# FPGA_Power.net
KiCad netlist of a schematic drawn in Altium Designer
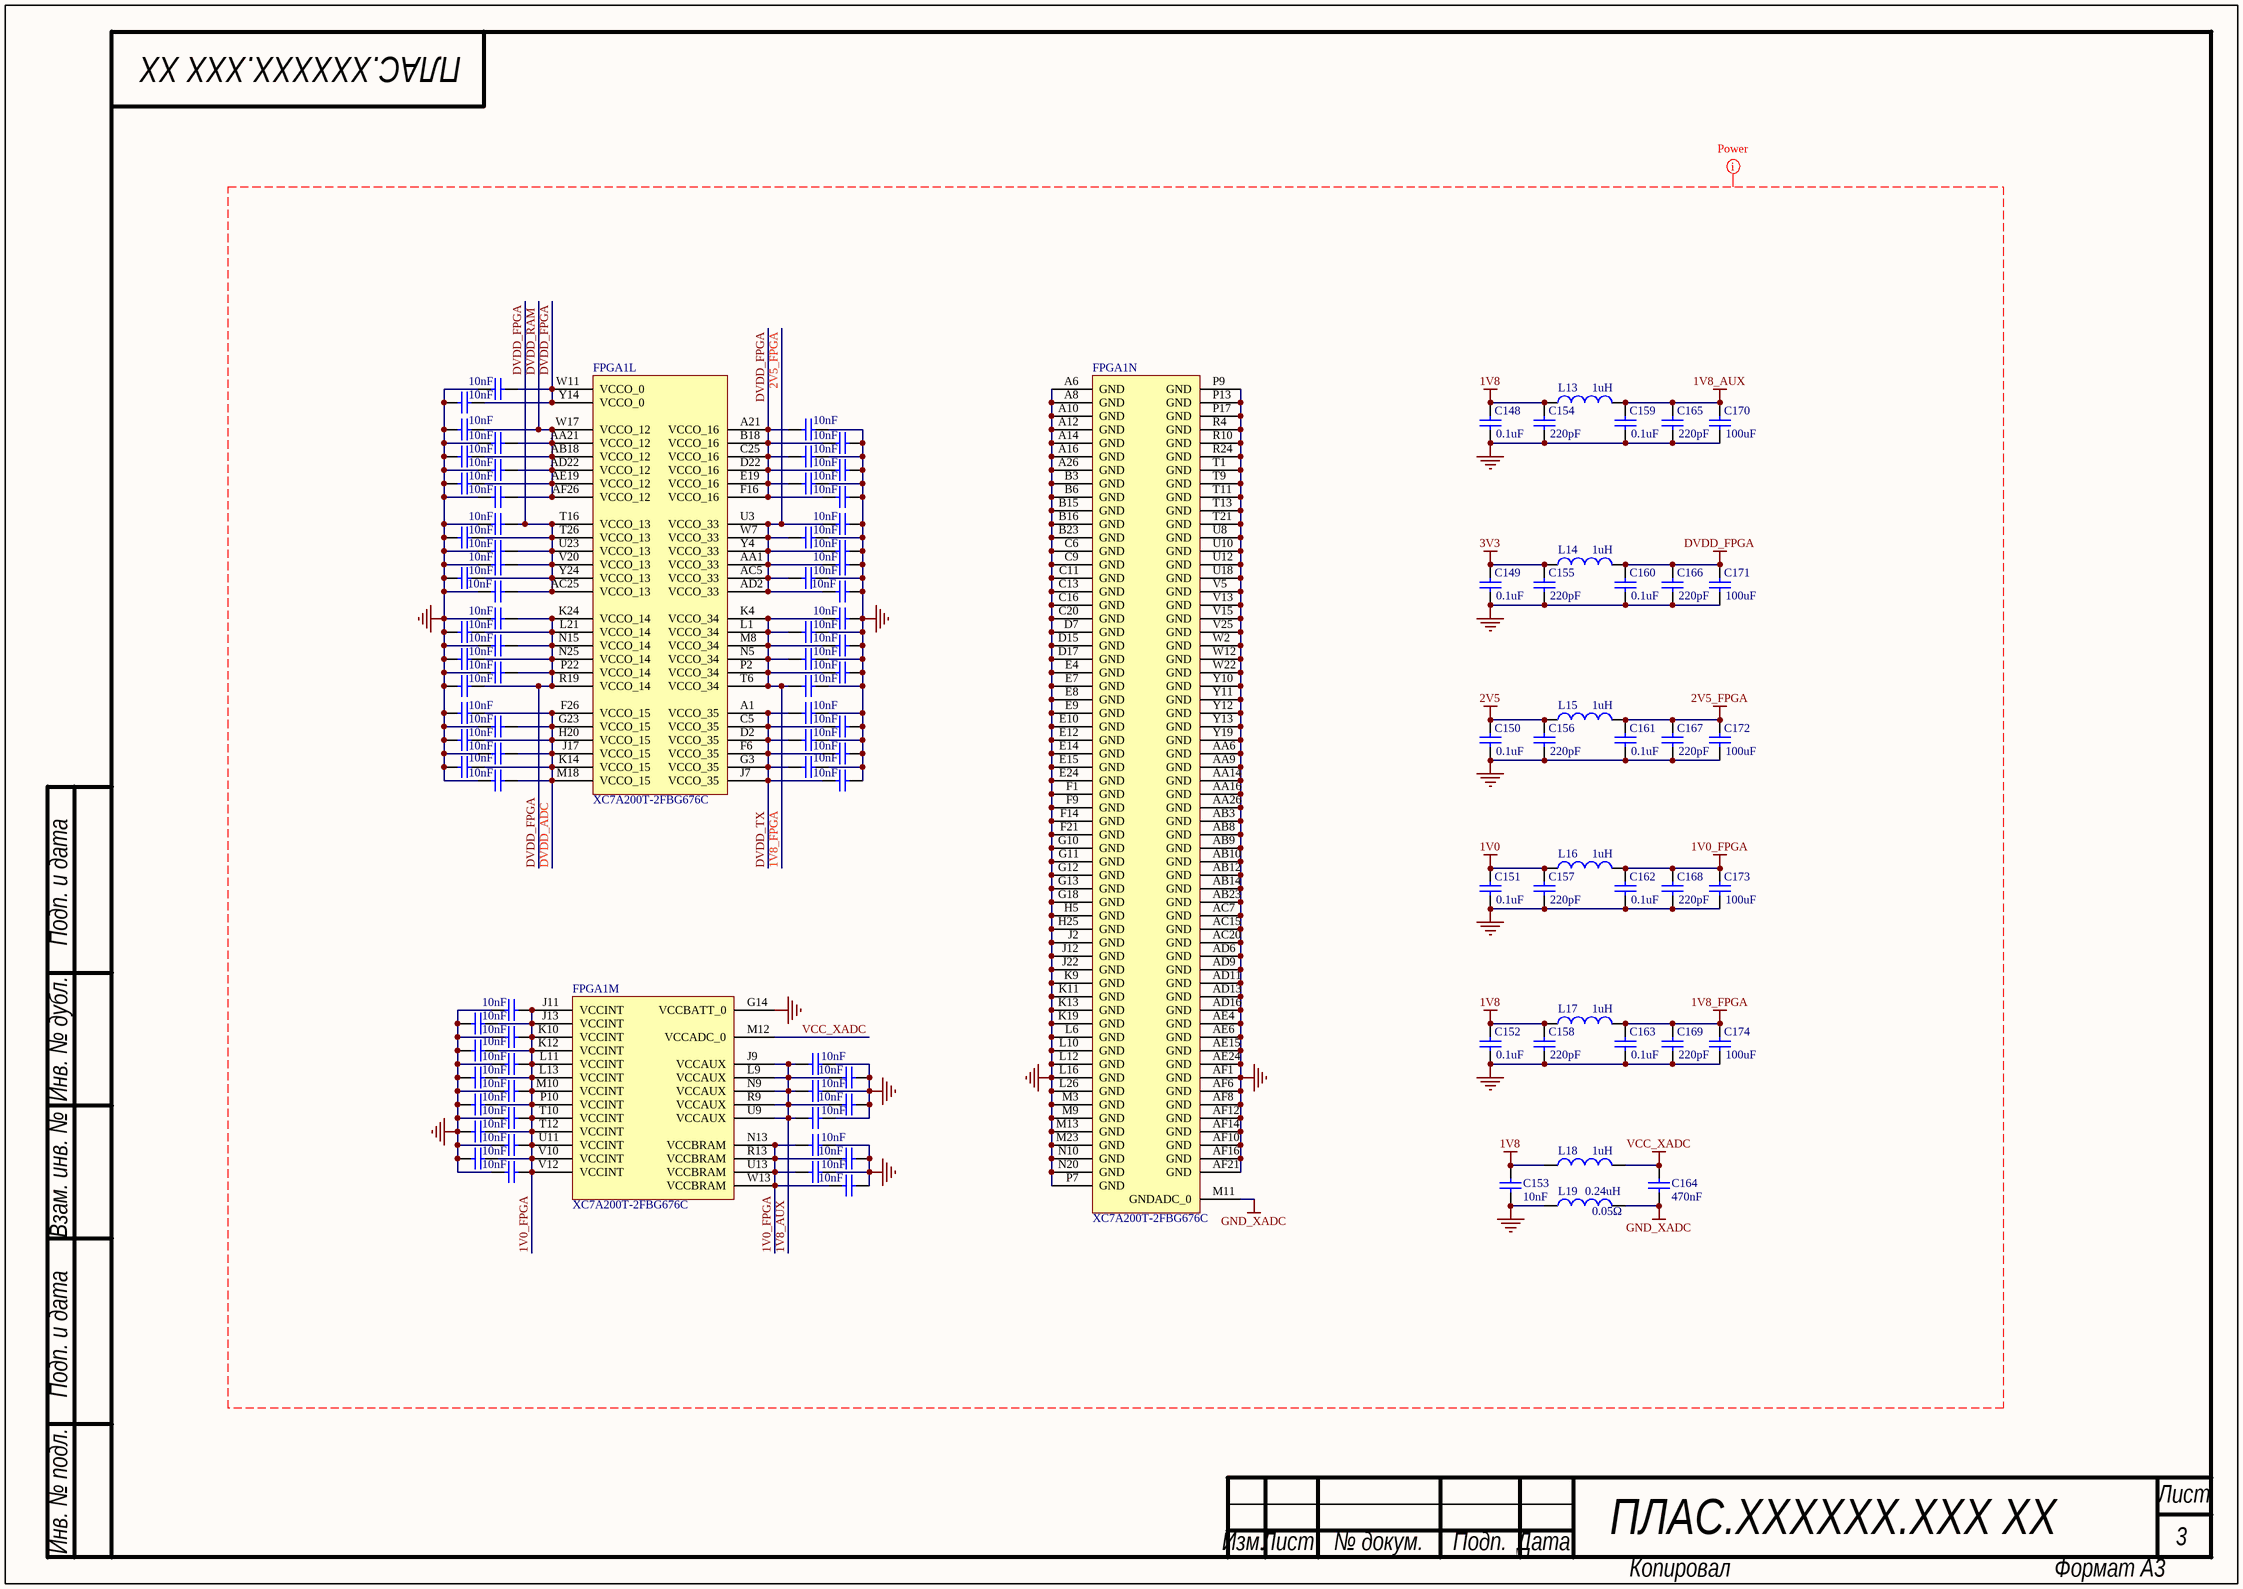
[diagram p0: FPGA_Power.SchDoc]

(export (version "E")
  (design (tool "Eeschema 10.0.6"))
  (components
    (comp (ref "C76")
      (value "10nF")
      (footprint "С0402")
      (description "Cer Cap Small")
      (fields (field (name "MANUFACTURER") "Murata") (field (name "VOLTAGE") "25V"))
      (libsource (lib "") (part "Cer Cap_1"))
    )
    (comp (ref "C77")
      (value "10nF")
      (footprint "С0402")
      (description "Cer Cap Small")
      (fields (field (name "MANUFACTURER") "Murata") (field (name "VOLTAGE") "25V"))
      (libsource (lib "USRP2_Clone") (part "Cer Cap"))
    )
    (comp (ref "C78")
      (value "10nF")
      (footprint "С0402")
      (description "Cer Cap Small")
      (fields (field (name "MANUFACTURER") "Murata") (field (name "VOLTAGE") "25V"))
      (libsource (lib "USRP2_Clone") (part "Cer Cap"))
    )
    (comp (ref "C79")
      (value "10nF")
      (footprint "С0402")
      (description "Cer Cap Small")
      (fields (field (name "MANUFACTURER") "Murata") (field (name "VOLTAGE") "25V"))
      (libsource (lib "USRP2_Clone") (part "Cer Cap"))
    )
    (comp (ref "C80")
      (value "10nF")
      (footprint "С0402")
      (description "Cer Cap Small")
      (fields (field (name "MANUFACTURER") "Murata") (field (name "VOLTAGE") "25V"))
      (libsource (lib "USRP2_Clone") (part "Cer Cap"))
    )
    (comp (ref "C81")
      (value "10nF")
      (footprint "С0402")
      (description "Cer Cap Small")
      (fields (field (name "MANUFACTURER") "Murata") (field (name "VOLTAGE") "25V"))
      (libsource (lib "USRP2_Clone") (part "Cer Cap"))
    )
    (comp (ref "C82")
      (value "10nF")
      (footprint "С0402")
      (description "Cer Cap Small")
      (fields (field (name "MANUFACTURER") "Murata") (field (name "VOLTAGE") "25V"))
      (libsource (lib "USRP2_Clone") (part "Cer Cap"))
    )
    (comp (ref "C83")
      (value "10nF")
      (footprint "С0402")
      (description "Cer Cap Small")
      (fields (field (name "MANUFACTURER") "Murata") (field (name "VOLTAGE") "25V"))
      (libsource (lib "USRP2_Clone") (part "Cer Cap"))
    )
    (comp (ref "C84")
      (value "10nF")
      (footprint "С0402")
      (description "Cer Cap Small")
      (fields (field (name "MANUFACTURER") "Murata") (field (name "VOLTAGE") "25V"))
      (libsource (lib "USRP2_Clone") (part "Cer Cap"))
    )
    (comp (ref "C85")
      (value "10nF")
      (footprint "С0402")
      (description "Cer Cap Small")
      (fields (field (name "MANUFACTURER") "Murata") (field (name "VOLTAGE") "25V"))
      (libsource (lib "") (part "Cer Cap_1"))
    )
    (comp (ref "C86")
      (value "10nF")
      (footprint "С0402")
      (description "Cer Cap Small")
      (fields (field (name "MANUFACTURER") "Murata") (field (name "VOLTAGE") "25V"))
      (libsource (lib "") (part "Cer Cap_1"))
    )
    (comp (ref "C87")
      (value "10nF")
      (footprint "С0402")
      (description "Cer Cap Small")
      (fields (field (name "MANUFACTURER") "Murata") (field (name "VOLTAGE") "25V"))
      (libsource (lib "") (part "Cer Cap_1"))
    )
    (comp (ref "C88")
      (value "10nF")
      (footprint "С0402")
      (description "Cer Cap Small")
      (fields (field (name "MANUFACTURER") "Murata") (field (name "VOLTAGE") "25V"))
      (libsource (lib "USRP2_Clone") (part "Cer Cap"))
    )
    (comp (ref "C89")
      (value "10nF")
      (footprint "С0402")
      (description "Cer Cap Small")
      (fields (field (name "MANUFACTURER") "Murata") (field (name "VOLTAGE") "25V"))
      (libsource (lib "USRP2_Clone") (part "Cer Cap"))
    )
    (comp (ref "C90")
      (value "10nF")
      (footprint "С0402")
      (description "Cer Cap Small")
      (fields (field (name "MANUFACTURER") "Murata") (field (name "VOLTAGE") "25V"))
      (libsource (lib "USRP2_Clone") (part "Cer Cap"))
    )
    (comp (ref "C91")
      (value "10nF")
      (footprint "С0402")
      (description "Cer Cap Small")
      (fields (field (name "MANUFACTURER") "Murata") (field (name "VOLTAGE") "25V"))
      (libsource (lib "USRP2_Clone") (part "Cer Cap"))
    )
    (comp (ref "C92")
      (value "10nF")
      (footprint "С0402")
      (description "Cer Cap Small")
      (fields (field (name "MANUFACTURER") "Murata") (field (name "VOLTAGE") "25V"))
      (libsource (lib "") (part "Cer Cap_1"))
    )
    (comp (ref "C93")
      (value "10nF")
      (footprint "С0402")
      (description "Cer Cap Small")
      (fields (field (name "MANUFACTURER") "Murata") (field (name "VOLTAGE") "25V"))
      (libsource (lib "USRP2_Clone") (part "Cer Cap"))
    )
    (comp (ref "C94")
      (value "10nF")
      (footprint "С0402")
      (description "Cer Cap Small")
      (fields (field (name "MANUFACTURER") "Murata") (field (name "VOLTAGE") "25V"))
      (libsource (lib "") (part "Cer Cap_1"))
    )
    (comp (ref "C95")
      (value "10nF")
      (footprint "С0402")
      (description "Cer Cap Small")
      (fields (field (name "MANUFACTURER") "Murata") (field (name "VOLTAGE") "25V"))
      (libsource (lib "USRP2_Clone") (part "Cer Cap"))
    )
    (comp (ref "C96")
      (value "10nF")
      (footprint "С0402")
      (description "Cer Cap Small")
      (fields (field (name "MANUFACTURER") "Murata") (field (name "VOLTAGE") "25V"))
      (libsource (lib "USRP2_Clone") (part "Cer Cap"))
    )
    (comp (ref "C97")
      (value "10nF")
      (footprint "С0402")
      (description "Cer Cap Small")
      (fields (field (name "MANUFACTURER") "Murata") (field (name "VOLTAGE") "25V"))
      (libsource (lib "USRP2_Clone") (part "Cer Cap"))
    )
    (comp (ref "C98")
      (value "10nF")
      (footprint "С0402")
      (description "Cer Cap Small")
      (fields (field (name "MANUFACTURER") "Murata") (field (name "VOLTAGE") "25V"))
      (libsource (lib "USRP2_Clone") (part "Cer Cap"))
    )
    (comp (ref "C99")
      (value "10nF")
      (footprint "С0402")
      (description "Cer Cap Small")
      (fields (field (name "MANUFACTURER") "Murata") (field (name "VOLTAGE") "25V"))
      (libsource (lib "") (part "Cer Cap_1"))
    )
    (comp (ref "C100")
      (value "10nF")
      (footprint "С0402")
      (description "Cer Cap Small")
      (fields (field (name "MANUFACTURER") "Murata") (field (name "VOLTAGE") "25V"))
      (libsource (lib "USRP2_Clone") (part "Cer Cap"))
    )
    (comp (ref "C101")
      (value "10nF")
      (footprint "С0402")
      (description "Cer Cap Small")
      (fields (field (name "MANUFACTURER") "Murata") (field (name "VOLTAGE") "25V"))
      (libsource (lib "USRP2_Clone") (part "Cer Cap"))
    )
    (comp (ref "C102")
      (value "10nF")
      (footprint "С0402")
      (description "Cer Cap Small")
      (fields (field (name "MANUFACTURER") "Murata") (field (name "VOLTAGE") "25V"))
      (libsource (lib "USRP2_Clone") (part "Cer Cap"))
    )
    (comp (ref "C103")
      (value "10nF")
      (footprint "С0402")
      (description "Cer Cap Small")
      (fields (field (name "MANUFACTURER") "Murata") (field (name "VOLTAGE") "25V"))
      (libsource (lib "USRP2_Clone") (part "Cer Cap"))
    )
    (comp (ref "C104")
      (value "10nF")
      (footprint "С0402")
      (description "Cer Cap Small")
      (fields (field (name "MANUFACTURER") "Murata") (field (name "VOLTAGE") "25V"))
      (libsource (lib "USRP2_Clone") (part "Cer Cap"))
    )
    (comp (ref "C105")
      (value "10nF")
      (footprint "С0402")
      (description "Cer Cap Small")
      (fields (field (name "MANUFACTURER") "Murata") (field (name "VOLTAGE") "25V"))
      (libsource (lib "") (part "Cer Cap_1"))
    )
    (comp (ref "C106")
      (value "10nF")
      (footprint "С0402")
      (description "Cer Cap Small")
      (fields (field (name "MANUFACTURER") "Murata") (field (name "VOLTAGE") "25V"))
      (libsource (lib "") (part "Cer Cap_1"))
    )
    (comp (ref "C107")
      (value "10nF")
      (footprint "С0402")
      (description "Cer Cap Small")
      (fields (field (name "MANUFACTURER") "Murata") (field (name "VOLTAGE") "25V"))
      (libsource (lib "") (part "Cer Cap_1"))
    )
    (comp (ref "C108")
      (value "10nF")
      (footprint "С0402")
      (description "Cer Cap Small")
      (fields (field (name "MANUFACTURER") "Murata") (field (name "VOLTAGE") "25V"))
      (libsource (lib "") (part "Cer Cap_1"))
    )
    (comp (ref "C109")
      (value "10nF")
      (footprint "С0402")
      (description "Cer Cap Small")
      (fields (field (name "MANUFACTURER") "Murata") (field (name "VOLTAGE") "25V"))
      (libsource (lib "") (part "Cer Cap_1"))
    )
    (comp (ref "C110")
      (value "10nF")
      (footprint "С0402")
      (description "Cer Cap Small")
      (fields (field (name "MANUFACTURER") "Murata") (field (name "VOLTAGE") "25V"))
      (libsource (lib "USRP2_Clone") (part "Cer Cap"))
    )
    (comp (ref "C111")
      (value "10nF")
      (footprint "С0402")
      (description "Cer Cap Small")
      (fields (field (name "MANUFACTURER") "Murata") (field (name "VOLTAGE") "25V"))
      (libsource (lib "") (part "Cer Cap_1"))
    )
    (comp (ref "C112")
      (value "10nF")
      (footprint "С0402")
      (description "Cer Cap Small")
      (fields (field (name "MANUFACTURER") "Murata") (field (name "VOLTAGE") "25V"))
      (libsource (lib "") (part "Cer Cap_1"))
    )
    (comp (ref "C113")
      (value "10nF")
      (footprint "С0402")
      (description "Cer Cap Small")
      (fields (field (name "MANUFACTURER") "Murata") (field (name "VOLTAGE") "25V"))
      (libsource (lib "USRP2_Clone") (part "Cer Cap"))
    )
    (comp (ref "C114")
      (value "10nF")
      (footprint "С0402")
      (description "Cer Cap Small")
      (fields (field (name "MANUFACTURER") "Murata") (field (name "VOLTAGE") "25V"))
      (libsource (lib "USRP2_Clone") (part "Cer Cap"))
    )
    (comp (ref "C115")
      (value "10nF")
      (footprint "С0402")
      (description "Cer Cap Small")
      (fields (field (name "MANUFACTURER") "Murata") (field (name "VOLTAGE") "25V"))
      (libsource (lib "USRP2_Clone") (part "Cer Cap"))
    )
    (comp (ref "C116")
      (value "10nF")
      (footprint "С0402")
      (description "Cer Cap Small")
      (fields (field (name "MANUFACTURER") "Murata") (field (name "VOLTAGE") "25V"))
      (libsource (lib "USRP2_Clone") (part "Cer Cap"))
    )
    (comp (ref "C117")
      (value "10nF")
      (footprint "С0402")
      (description "Cer Cap Small")
      (fields (field (name "MANUFACTURER") "Murata") (field (name "VOLTAGE") "25V"))
      (libsource (lib "USRP2_Clone") (part "Cer Cap"))
    )
    (comp (ref "C118")
      (value "10nF")
      (footprint "С0402")
      (description "Cer Cap Small")
      (fields (field (name "MANUFACTURER") "Murata") (field (name "VOLTAGE") "25V"))
      (libsource (lib "USRP2_Clone") (part "Cer Cap"))
    )
    (comp (ref "C119")
      (value "10nF")
      (footprint "С0402")
      (description "Cer Cap Small")
      (fields (field (name "MANUFACTURER") "Murata") (field (name "VOLTAGE") "25V"))
      (libsource (lib "USRP2_Clone") (part "Cer Cap"))
    )
    (comp (ref "C120")
      (value "10nF")
      (footprint "С0402")
      (description "Cer Cap Small")
      (fields (field (name "MANUFACTURER") "Murata") (field (name "VOLTAGE") "25V"))
      (libsource (lib "USRP2_Clone") (part "Cer Cap"))
    )
    (comp (ref "C121")
      (value "10nF")
      (footprint "С0402")
      (description "Cer Cap Small")
      (fields (field (name "MANUFACTURER") "Murata") (field (name "VOLTAGE") "25V"))
      (libsource (lib "USRP2_Clone") (part "Cer Cap"))
    )
    (comp (ref "C122")
      (value "10nF")
      (footprint "С0402")
      (description "Cer Cap Small")
      (fields (field (name "MANUFACTURER") "Murata") (field (name "VOLTAGE") "25V"))
      (libsource (lib "USRP2_Clone") (part "Cer Cap"))
    )
    (comp (ref "C123")
      (value "10nF")
      (footprint "С0402")
      (description "Cer Cap Small")
      (fields (field (name "MANUFACTURER") "Murata") (field (name "VOLTAGE") "25V"))
      (libsource (lib "USRP2_Clone") (part "Cer Cap"))
    )
    (comp (ref "C124")
      (value "10nF")
      (footprint "С0402")
      (description "Cer Cap Small")
      (fields (field (name "MANUFACTURER") "Murata") (field (name "VOLTAGE") "25V"))
      (libsource (lib "USRP2_Clone") (part "Cer Cap"))
    )
    (comp (ref "C125")
      (value "10nF")
      (footprint "С0402")
      (description "Cer Cap Small")
      (fields (field (name "MANUFACTURER") "Murata") (field (name "VOLTAGE") "25V"))
      (libsource (lib "USRP2_Clone") (part "Cer Cap"))
    )
    (comp (ref "C126")
      (value "10nF")
      (footprint "С0402")
      (description "Cer Cap Small")
      (fields (field (name "MANUFACTURER") "Murata") (field (name "VOLTAGE") "25V"))
      (libsource (lib "") (part "Cer Cap_1"))
    )
    (comp (ref "C127")
      (value "10nF")
      (footprint "С0402")
      (description "Cer Cap Small")
      (fields (field (name "MANUFACTURER") "Murata") (field (name "VOLTAGE") "25V"))
      (libsource (lib "") (part "Cer Cap_1"))
    )
    (comp (ref "C128")
      (value "10nF")
      (footprint "С0402")
      (description "Cer Cap Small")
      (fields (field (name "MANUFACTURER") "Murata") (field (name "VOLTAGE") "25V"))
      (libsource (lib "USRP2_Clone") (part "Cer Cap"))
    )
    (comp (ref "C129")
      (value "10nF")
      (footprint "С0402")
      (description "Cer Cap Small")
      (fields (field (name "MANUFACTURER") "Murata") (field (name "VOLTAGE") "25V"))
      (libsource (lib "") (part "Cer Cap_1"))
    )
    (comp (ref "C130")
      (value "10nF")
      (footprint "С0402")
      (description "Cer Cap Small")
      (fields (field (name "MANUFACTURER") "Murata") (field (name "VOLTAGE") "25V"))
      (libsource (lib "USRP2_Clone") (part "Cer Cap"))
    )
    (comp (ref "C131")
      (value "10nF")
      (footprint "С0402")
      (description "Cer Cap Small")
      (fields (field (name "MANUFACTURER") "Murata") (field (name "VOLTAGE") "25V"))
      (libsource (lib "USRP2_Clone") (part "Cer Cap"))
    )
    (comp (ref "C132")
      (value "10nF")
      (footprint "С0402")
      (description "Cer Cap Small")
      (fields (field (name "MANUFACTURER") "Murata") (field (name "VOLTAGE") "25V"))
      (libsource (lib "USRP2_Clone") (part "Cer Cap"))
    )
    (comp (ref "C133")
      (value "10nF")
      (footprint "С0402")
      (description "Cer Cap Small")
      (fields (field (name "MANUFACTURER") "Murata") (field (name "VOLTAGE") "25V"))
      (libsource (lib "USRP2_Clone") (part "Cer Cap"))
    )
    (comp (ref "C134")
      (value "10nF")
      (footprint "С0402")
      (description "Cer Cap Small")
      (fields (field (name "MANUFACTURER") "Murata") (field (name "VOLTAGE") "25V"))
      (libsource (lib "USRP2_Clone") (part "Cer Cap"))
    )
    (comp (ref "C135")
      (value "10nF")
      (footprint "С0402")
      (description "Cer Cap Small")
      (fields (field (name "MANUFACTURER") "Murata") (field (name "VOLTAGE") "25V"))
      (libsource (lib "USRP2_Clone") (part "Cer Cap"))
    )
    (comp (ref "C136")
      (value "10nF")
      (footprint "С0402")
      (description "Cer Cap Small")
      (fields (field (name "MANUFACTURER") "Murata") (field (name "VOLTAGE") "25V"))
      (libsource (lib "") (part "Cer Cap_1"))
    )
    (comp (ref "C137")
      (value "10nF")
      (footprint "С0402")
      (description "Cer Cap Small")
      (fields (field (name "MANUFACTURER") "Murata") (field (name "VOLTAGE") "25V"))
      (libsource (lib "USRP2_Clone") (part "Cer Cap"))
    )
    (comp (ref "C138")
      (value "10nF")
      (footprint "С0402")
      (description "Cer Cap Small")
      (fields (field (name "MANUFACTURER") "Murata") (field (name "VOLTAGE") "25V"))
      (libsource (lib "USRP2_Clone") (part "Cer Cap"))
    )
    (comp (ref "C139")
      (value "10nF")
      (footprint "С0402")
      (description "Cer Cap Small")
      (fields (field (name "MANUFACTURER") "Murata") (field (name "VOLTAGE") "25V"))
      (libsource (lib "USRP2_Clone") (part "Cer Cap"))
    )
    (comp (ref "C140")
      (value "10nF")
      (footprint "С0402")
      (description "Cer Cap Small")
      (fields (field (name "MANUFACTURER") "Murata") (field (name "VOLTAGE") "25V"))
      (libsource (lib "USRP2_Clone") (part "Cer Cap"))
    )
    (comp (ref "C141")
      (value "10nF")
      (footprint "С0402")
      (description "Cer Cap Small")
      (fields (field (name "MANUFACTURER") "Murata") (field (name "VOLTAGE") "25V"))
      (libsource (lib "USRP2_Clone") (part "Cer Cap"))
    )
    (comp (ref "C142")
      (value "10nF")
      (footprint "С0402")
      (description "Cer Cap Small")
      (fields (field (name "MANUFACTURER") "Murata") (field (name "VOLTAGE") "25V"))
      (libsource (lib "USRP2_Clone") (part "Cer Cap"))
    )
    (comp (ref "C143")
      (value "10nF")
      (footprint "С0402")
      (description "Cer Cap Small")
      (fields (field (name "MANUFACTURER") "Murata") (field (name "VOLTAGE") "25V"))
      (libsource (lib "USRP2_Clone") (part "Cer Cap"))
    )
    (comp (ref "C144")
      (value "10nF")
      (footprint "С0402")
      (description "Cer Cap Small")
      (fields (field (name "MANUFACTURER") "Murata") (field (name "VOLTAGE") "25V"))
      (libsource (lib "") (part "Cer Cap_1"))
    )
    (comp (ref "C145")
      (value "10nF")
      (footprint "С0402")
      (description "Cer Cap Small")
      (fields (field (name "MANUFACTURER") "Murata") (field (name "VOLTAGE") "25V"))
      (libsource (lib "USRP2_Clone") (part "Cer Cap"))
    )
    (comp (ref "C146")
      (value "10nF")
      (footprint "С0402")
      (description "Cer Cap Small")
      (fields (field (name "MANUFACTURER") "Murata") (field (name "VOLTAGE") "25V"))
      (libsource (lib "USRP2_Clone") (part "Cer Cap"))
    )
    (comp (ref "C147")
      (value "10nF")
      (footprint "С0402")
      (description "Cer Cap Small")
      (fields (field (name "MANUFACTURER") "Murata") (field (name "VOLTAGE") "25V"))
      (libsource (lib "USRP2_Clone") (part "Cer Cap"))
    )
    (comp (ref "C148")
      (value "0.1uF")
      (footprint "C0603")
      (description "Cer Cap Small")
      (fields (field (name "MANUFACTURER") "Murata") (field (name "VOLTAGE") "16V"))
      (libsource (lib "") (part "Cer Cap_1"))
    )
    (comp (ref "C149")
      (value "0.1uF")
      (footprint "C0603")
      (description "Cer Cap Small")
      (fields (field (name "MANUFACTURER") "Murata") (field (name "VOLTAGE") "16V"))
      (libsource (lib "") (part "Cer Cap_1"))
    )
    (comp (ref "C150")
      (value "0.1uF")
      (footprint "C0603")
      (description "Cer Cap Small")
      (fields (field (name "MANUFACTURER") "Murata") (field (name "VOLTAGE") "16V"))
      (libsource (lib "") (part "Cer Cap_1"))
    )
    (comp (ref "C151")
      (value "0.1uF")
      (footprint "C0603")
      (description "Cer Cap Small")
      (fields (field (name "MANUFACTURER") "Murata") (field (name "VOLTAGE") "16V"))
      (libsource (lib "") (part "Cer Cap_1"))
    )
    (comp (ref "C152")
      (value "0.1uF")
      (footprint "C0603")
      (description "Cer Cap Small")
      (fields (field (name "MANUFACTURER") "Murata") (field (name "VOLTAGE") "16V"))
      (libsource (lib "USRP2_Clone") (part "Cer Cap"))
    )
    (comp (ref "C153")
      (value "10nF")
      (footprint "С0402")
      (description "Cer Cap Small")
      (fields (field (name "MANUFACTURER") "Murata") (field (name "VOLTAGE") "25V"))
      (libsource (lib "USRP2_Clone") (part "Cer Cap"))
    )
    (comp (ref "C154")
      (value "220pF")
      (footprint "C0603")
      (description "Cer Cap Small")
      (fields (field (name "MANUFACTURER") "Murata") (field (name "VOLTAGE") "16V"))
      (libsource (lib "") (part "Cer Cap_1"))
    )
    (comp (ref "C155")
      (value "220pF")
      (footprint "C0603")
      (description "Cer Cap Small")
      (fields (field (name "MANUFACTURER") "Murata") (field (name "VOLTAGE") "16V"))
      (libsource (lib "") (part "Cer Cap_1"))
    )
    (comp (ref "C156")
      (value "220pF")
      (footprint "C0603")
      (description "Cer Cap Small")
      (fields (field (name "MANUFACTURER") "Murata") (field (name "VOLTAGE") "16V"))
      (libsource (lib "") (part "Cer Cap_1"))
    )
    (comp (ref "C157")
      (value "220pF")
      (footprint "C0603")
      (description "Cer Cap Small")
      (fields (field (name "MANUFACTURER") "Murata") (field (name "VOLTAGE") "16V"))
      (libsource (lib "") (part "Cer Cap_1"))
    )
    (comp (ref "C158")
      (value "220pF")
      (footprint "C0603")
      (description "Cer Cap Small")
      (fields (field (name "MANUFACTURER") "Murata") (field (name "VOLTAGE") "16V"))
      (libsource (lib "") (part "Cer Cap_1"))
    )
    (comp (ref "C159")
      (value "0.1uF")
      (footprint "C0603")
      (description "Cer Cap Small")
      (fields (field (name "MANUFACTURER") "Murata") (field (name "VOLTAGE") "16V"))
      (libsource (lib "") (part "Cer Cap_1"))
    )
    (comp (ref "C160")
      (value "0.1uF")
      (footprint "C0603")
      (description "Cer Cap Small")
      (fields (field (name "MANUFACTURER") "Murata") (field (name "VOLTAGE") "16V"))
      (libsource (lib "") (part "Cer Cap_1"))
    )
    (comp (ref "C161")
      (value "0.1uF")
      (footprint "C0603")
      (description "Cer Cap Small")
      (fields (field (name "MANUFACTURER") "Murata") (field (name "VOLTAGE") "16V"))
      (libsource (lib "") (part "Cer Cap_1"))
    )
    (comp (ref "C162")
      (value "0.1uF")
      (footprint "C0603")
      (description "Cer Cap Small")
      (fields (field (name "MANUFACTURER") "Murata") (field (name "VOLTAGE") "16V"))
      (libsource (lib "") (part "Cer Cap_1"))
    )
    (comp (ref "C163")
      (value "0.1uF")
      (footprint "C0603")
      (description "Cer Cap Small")
      (fields (field (name "MANUFACTURER") "Murata") (field (name "VOLTAGE") "16V"))
      (libsource (lib "") (part "Cer Cap_1"))
    )
    (comp (ref "C164")
      (value "470nF")
      (footprint "C0603")
      (description "Cer Cap Small")
      (fields (field (name "MANUFACTURER") "Murata") (field (name "VOLTAGE") "16V"))
      (libsource (lib "USRP2_Clone") (part "Cer Cap"))
    )
    (comp (ref "C165")
      (value "220pF")
      (footprint "C0603")
      (description "Cer Cap Small")
      (fields (field (name "MANUFACTURER") "Murata") (field (name "VOLTAGE") "16V"))
      (libsource (lib "") (part "Cer Cap_1"))
    )
    (comp (ref "C166")
      (value "220pF")
      (footprint "C0603")
      (description "Cer Cap Small")
      (fields (field (name "MANUFACTURER") "Murata") (field (name "VOLTAGE") "16V"))
      (libsource (lib "") (part "Cer Cap_1"))
    )
    (comp (ref "C167")
      (value "220pF")
      (footprint "C0603")
      (description "Cer Cap Small")
      (fields (field (name "MANUFACTURER") "Murata") (field (name "VOLTAGE") "16V"))
      (libsource (lib "") (part "Cer Cap_1"))
    )
    (comp (ref "C168")
      (value "220pF")
      (footprint "C0603")
      (description "Cer Cap Small")
      (fields (field (name "MANUFACTURER") "Murata") (field (name "VOLTAGE") "16V"))
      (libsource (lib "") (part "Cer Cap_1"))
    )
    (comp (ref "C169")
      (value "220pF")
      (footprint "C0603")
      (description "Cer Cap Small")
      (fields (field (name "MANUFACTURER") "Murata") (field (name "VOLTAGE") "16V"))
      (libsource (lib "") (part "Cer Cap_1"))
    )
    (comp (ref "C170")
      (value "100uF")
      (footprint "C1210")
      (description "Cer Cap Large")
      (fields (field (name "MANUFACTURER") "Murata") (field (name "TOLERANCE") "20%"))
      (libsource (lib "USRP2_Clone") (part "Cap uF"))
    )
    (comp (ref "C171")
      (value "100uF")
      (footprint "C1210")
      (description "Cer Cap Large")
      (fields (field (name "MANUFACTURER") "Murata") (field (name "TOLERANCE") "20%"))
      (libsource (lib "") (part "Cap uF_1"))
    )
    (comp (ref "C172")
      (value "100uF")
      (footprint "C1210")
      (description "Cer Cap Large")
      (fields (field (name "MANUFACTURER") "Murata") (field (name "TOLERANCE") "20%"))
      (libsource (lib "USRP2_Clone") (part "Cap uF"))
    )
    (comp (ref "C173")
      (value "100uF")
      (footprint "C1210")
      (description "Cer Cap Large")
      (fields (field (name "MANUFACTURER") "Murata") (field (name "TOLERANCE") "20%"))
      (libsource (lib "USRP2_Clone") (part "Cap uF"))
    )
    (comp (ref "C174")
      (value "100uF")
      (footprint "C1210")
      (description "Cer Cap Large")
      (fields (field (name "MANUFACTURER") "Murata") (field (name "TOLERANCE") "20%"))
      (libsource (lib "") (part "Cap uF_1"))
    )
    (comp (ref "FPGA1")
      (value "XC7A200T-2FBG676C")
      (footprint "FGG676")
      (description "Artix-7 FPGA, 400 User I/Os, 8 GTP, 676-Ball BGA, Speed Grade 2, Commercial Grade, Pb-Free")
      (fields (field (name "GENERIC PART NUMBER") "XC7A200T") (field (name "MANUFACTURER") "Xilinx"))
      (libsource (lib "USRP2_Clone") (part "XC7A200T-2FBG676C"))
    )
    (comp (ref "L13")
      (value "1uH")
      (footprint "L1210_Murata LQH")
      (description "Inductor_Power_Lines")
      (fields (field (name "TOLERANCE") "5%") (field (name "MANUFACTURER") "Murata"))
      (libsource (lib "USRP2_Clone") (part "Inductor_LF"))
    )
    (comp (ref "L14")
      (value "1uH")
      (footprint "L1210_Murata LQH")
      (description "Inductor_Power_Lines")
      (fields (field (name "TOLERANCE") "5%") (field (name "MANUFACTURER") "Murata"))
      (libsource (lib "") (part "Inductor_LF_1"))
    )
    (comp (ref "L15")
      (value "1uH")
      (footprint "L1210_Murata LQH")
      (description "Inductor_Power_Lines")
      (fields (field (name "TOLERANCE") "5%") (field (name "MANUFACTURER") "Murata"))
      (libsource (lib "USRP2_Clone") (part "Inductor_LF"))
    )
    (comp (ref "L16")
      (value "1uH")
      (footprint "L1210_Murata LQH")
      (description "Inductor_Power_Lines")
      (fields (field (name "TOLERANCE") "5%") (field (name "MANUFACTURER") "Murata"))
      (libsource (lib "USRP2_Clone") (part "Inductor_LF"))
    )
    (comp (ref "L17")
      (value "1uH")
      (footprint "L1210_Murata LQH")
      (description "Inductor_Power_Lines")
      (fields (field (name "TOLERANCE") "5%") (field (name "MANUFACTURER") "Murata"))
      (libsource (lib "USRP2_Clone") (part "Inductor_LF"))
    )
    (comp (ref "L18")
      (value "1uH")
      (footprint "L1206_Murata")
      (description "Inductor_Power_Lines")
      (fields (field (name "TOLERANCE") "5%") (field (name "MANUFACTURER") "Murata"))
      (libsource (lib "USRP2_Clone") (part "Inductor_LF"))
    )
    (comp (ref "L19")
      (value "0.24uH")
      (footprint "L0805_Murata_LQG")
      (description "Inductor_Power_Lines")
      (fields
        (field (name "TOLERANCE") "±20%")
        (field (name "MANUFACTURER") "Murata")
        (field (name "DCR") "0.05Ω")
      )
      (libsource (lib "") (part "Inductor_LF_1"))
    )
  )
  (nets
    (net (code "1") (name "/DVDD_ADC") (class "Default")
      (node (ref "C105") (pin "2") (pinfunction "2_2") (pintype "passive"))
      (node (ref "C106") (pin "2") (pinfunction "2_2") (pintype "passive"))
      (node (ref "C107") (pin "2") (pinfunction "2_2") (pintype "passive"))
      (node (ref "C85") (pin "2") (pinfunction "2_2") (pintype "passive"))
      (node (ref "C86") (pin "2") (pinfunction "2_2") (pintype "passive"))
      (node (ref "C87") (pin "2") (pinfunction "2_2") (pintype "passive"))
      (node (ref "FPGA1") (pin "F26") (pinfunction "VCCO_15_F26") (pintype "power_in"))
      (node (ref "FPGA1") (pin "G23") (pinfunction "VCCO_15_G23") (pintype "power_in"))
      (node (ref "FPGA1") (pin "H20") (pinfunction "VCCO_15_H20") (pintype "power_in"))
      (node (ref "FPGA1") (pin "J17") (pinfunction "VCCO_15_J17") (pintype "power_in"))
      (node (ref "FPGA1") (pin "K14") (pinfunction "VCCO_15_K14") (pintype "power_in"))
      (node (ref "FPGA1") (pin "M18") (pinfunction "VCCO_15_M18") (pintype "power_in"))
    )
    (net (code "2") (name "/DVDD_RAM") (class "Default")
      (node (ref "C77") (pin "1") (pinfunction "1_1") (pintype "passive"))
      (node (ref "C78") (pin "1") (pinfunction "1_1") (pintype "passive"))
      (node (ref "C79") (pin "1") (pinfunction "1_1") (pintype "passive"))
      (node (ref "C95") (pin "1") (pinfunction "1_1") (pintype "passive"))
      (node (ref "C96") (pin "1") (pinfunction "1_1") (pintype "passive"))
      (node (ref "C97") (pin "1") (pinfunction "1_1") (pintype "passive"))
      (node (ref "FPGA1") (pin "AA21") (pinfunction "VCCO_12_AA21") (pintype "power_in"))
      (node (ref "FPGA1") (pin "AB18") (pinfunction "VCCO_12_AB18") (pintype "power_in"))
      (node (ref "FPGA1") (pin "AD22") (pinfunction "VCCO_12_AD22") (pintype "power_in"))
      (node (ref "FPGA1") (pin "AE19") (pinfunction "VCCO_12_AE19") (pintype "power_in"))
      (node (ref "FPGA1") (pin "AF26") (pinfunction "VCCO_12_AF26") (pintype "power_in"))
      (node (ref "FPGA1") (pin "W17") (pinfunction "VCCO_12_W17") (pintype "power_in"))
    )
    (net (code "3") (name "/DVDD_TX") (class "Default")
      (node (ref "C123") (pin "2") (pinfunction "2_2") (pintype "passive"))
      (node (ref "C124") (pin "2") (pinfunction "2_2") (pintype "passive"))
      (node (ref "C125") (pin "2") (pinfunction "2_2") (pintype "passive"))
      (node (ref "C141") (pin "2") (pinfunction "2_2") (pintype "passive"))
      (node (ref "C142") (pin "2") (pinfunction "2_2") (pintype "passive"))
      (node (ref "C143") (pin "2") (pinfunction "2_2") (pintype "passive"))
      (node (ref "FPGA1") (pin "A1") (pinfunction "VCCO_35_A1") (pintype "power_in"))
      (node (ref "FPGA1") (pin "C5") (pinfunction "VCCO_35_C5") (pintype "power_in"))
      (node (ref "FPGA1") (pin "D2") (pinfunction "VCCO_35_D2") (pintype "power_in"))
      (node (ref "FPGA1") (pin "F6") (pinfunction "VCCO_35_F6") (pintype "power_in"))
      (node (ref "FPGA1") (pin "G3") (pinfunction "VCCO_35_G3") (pintype "power_in"))
      (node (ref "FPGA1") (pin "J7") (pinfunction "VCCO_35_J7") (pintype "power_in"))
    )
    (net (code "4") (name "1V0") (class "Default")
      (node (ref "C151") (pin "1") (pinfunction "1_1") (pintype "passive"))
      (node (ref "C157") (pin "1") (pinfunction "1_1") (pintype "passive"))
      (node (ref "L16") (pin "2") (pinfunction "2_2") (pintype "passive"))
    )
    (net (code "5") (name "1V0_FPGA") (class "Default")
      (node (ref "C108") (pin "2") (pinfunction "2_2") (pintype "passive"))
      (node (ref "C109") (pin "2") (pinfunction "2_2") (pintype "passive"))
      (node (ref "C110") (pin "1") (pinfunction "1_1") (pintype "passive"))
      (node (ref "C111") (pin "2") (pinfunction "2_2") (pintype "passive"))
      (node (ref "C112") (pin "2") (pinfunction "2_2") (pintype "passive"))
      (node (ref "C113") (pin "1") (pinfunction "1_1") (pintype "passive"))
      (node (ref "C114") (pin "1") (pinfunction "1_1") (pintype "passive"))
      (node (ref "C129") (pin "1") (pinfunction "1_1") (pintype "passive"))
      (node (ref "C130") (pin "2") (pinfunction "2_2") (pintype "passive"))
      (node (ref "C146") (pin "2") (pinfunction "2_2") (pintype "passive"))
      (node (ref "C147") (pin "2") (pinfunction "2_2") (pintype "passive"))
      (node (ref "C162") (pin "1") (pinfunction "1_1") (pintype "passive"))
      (node (ref "C168") (pin "1") (pinfunction "1_1") (pintype "passive"))
      (node (ref "C173") (pin "2") (pinfunction "2_2") (pintype "passive"))
      (node (ref "C88") (pin "1") (pinfunction "1_1") (pintype "passive"))
      (node (ref "C89") (pin "1") (pinfunction "1_1") (pintype "passive"))
      (node (ref "C90") (pin "1") (pinfunction "1_1") (pintype "passive"))
      (node (ref "C91") (pin "1") (pinfunction "1_1") (pintype "passive"))
      (node (ref "C92") (pin "2") (pinfunction "2_2") (pintype "passive"))
      (node (ref "C93") (pin "1") (pinfunction "1_1") (pintype "passive"))
      (node (ref "FPGA1") (pin "J11") (pinfunction "VCCINT_J11") (pintype "power_in"))
      (node (ref "FPGA1") (pin "J13") (pinfunction "VCCINT_J13") (pintype "power_in"))
      (node (ref "FPGA1") (pin "K10") (pinfunction "VCCINT_K10") (pintype "power_in"))
      (node (ref "FPGA1") (pin "K12") (pinfunction "VCCINT_K12") (pintype "power_in"))
      (node (ref "FPGA1") (pin "L11") (pinfunction "VCCINT_L11") (pintype "power_in"))
      (node (ref "FPGA1") (pin "L13") (pinfunction "VCCINT_L13") (pintype "power_in"))
      (node (ref "FPGA1") (pin "M10") (pinfunction "VCCINT_M10") (pintype "power_in"))
      (node (ref "FPGA1") (pin "N13") (pinfunction "VCCBRAM_N13") (pintype "power_in"))
      (node (ref "FPGA1") (pin "P10") (pinfunction "VCCINT_P10") (pintype "power_in"))
      (node (ref "FPGA1") (pin "R13") (pinfunction "VCCBRAM_R13") (pintype "power_in"))
      (node (ref "FPGA1") (pin "T10") (pinfunction "VCCINT_T10") (pintype "power_in"))
      (node (ref "FPGA1") (pin "T12") (pinfunction "VCCINT_T12") (pintype "power_in"))
      (node (ref "FPGA1") (pin "U11") (pinfunction "VCCINT_U11") (pintype "power_in"))
      (node (ref "FPGA1") (pin "U13") (pinfunction "VCCBRAM_U13") (pintype "power_in"))
      (node (ref "FPGA1") (pin "V10") (pinfunction "VCCINT_V10") (pintype "power_in"))
      (node (ref "FPGA1") (pin "V12") (pinfunction "VCCINT_V12") (pintype "power_in"))
      (node (ref "FPGA1") (pin "W13") (pinfunction "VCCBRAM_W13") (pintype "power_in"))
      (node (ref "L16") (pin "1") (pinfunction "1_1") (pintype "passive"))
    )
    (net (code "6") (name "1V8") (class "Default")
      (node (ref "C148") (pin "1") (pinfunction "1_1") (pintype "passive"))
      (node (ref "C152") (pin "2") (pinfunction "2_2") (pintype "passive"))
      (node (ref "C153") (pin "2") (pinfunction "2_2") (pintype "passive"))
      (node (ref "C154") (pin "1") (pinfunction "1_1") (pintype "passive"))
      (node (ref "C158") (pin "1") (pinfunction "1_1") (pintype "passive"))
      (node (ref "L13") (pin "2") (pinfunction "2_2") (pintype "passive"))
      (node (ref "L17") (pin "2") (pinfunction "2_2") (pintype "passive"))
      (node (ref "L18") (pin "2") (pinfunction "2_2") (pintype "passive"))
    )
    (net (code "7") (name "1V8_AUX") (class "Default")
      (node (ref "C126") (pin "1") (pinfunction "1_1") (pintype "passive"))
      (node (ref "C127") (pin "1") (pinfunction "1_1") (pintype "passive"))
      (node (ref "C128") (pin "2") (pinfunction "2_2") (pintype "passive"))
      (node (ref "C144") (pin "1") (pinfunction "1_1") (pintype "passive"))
      (node (ref "C145") (pin "2") (pinfunction "2_2") (pintype "passive"))
      (node (ref "C159") (pin "1") (pinfunction "1_1") (pintype "passive"))
      (node (ref "C165") (pin "1") (pinfunction "1_1") (pintype "passive"))
      (node (ref "C170") (pin "2") (pinfunction "2_2") (pintype "passive"))
      (node (ref "FPGA1") (pin "J9") (pinfunction "VCCAUX_J9") (pintype "power_in"))
      (node (ref "FPGA1") (pin "L9") (pinfunction "VCCAUX_L9") (pintype "power_in"))
      (node (ref "FPGA1") (pin "N9") (pinfunction "VCCAUX_N9") (pintype "power_in"))
      (node (ref "FPGA1") (pin "R9") (pinfunction "VCCAUX_R9") (pintype "power_in"))
      (node (ref "FPGA1") (pin "U9") (pinfunction "VCCAUX_U9") (pintype "power_in"))
      (node (ref "L13") (pin "1") (pinfunction "1_1") (pintype "passive"))
    )
    (net (code "8") (name "1V8_FPGA") (class "Default")
      (node (ref "C120") (pin "2") (pinfunction "2_2") (pintype "passive"))
      (node (ref "C121") (pin "2") (pinfunction "2_2") (pintype "passive"))
      (node (ref "C122") (pin "2") (pinfunction "2_2") (pintype "passive"))
      (node (ref "C138") (pin "2") (pinfunction "2_2") (pintype "passive"))
      (node (ref "C139") (pin "2") (pinfunction "2_2") (pintype "passive"))
      (node (ref "C140") (pin "2") (pinfunction "2_2") (pintype "passive"))
      (node (ref "C163") (pin "1") (pinfunction "1_1") (pintype "passive"))
      (node (ref "C169") (pin "1") (pinfunction "1_1") (pintype "passive"))
      (node (ref "C174") (pin "1") (pinfunction "1_1") (pintype "passive"))
      (node (ref "FPGA1") (pin "K4") (pinfunction "VCCO_34_K4") (pintype "power_in"))
      (node (ref "FPGA1") (pin "L1") (pinfunction "VCCO_34_L1") (pintype "power_in"))
      (node (ref "FPGA1") (pin "M8") (pinfunction "VCCO_34_M8") (pintype "power_in"))
      (node (ref "FPGA1") (pin "N5") (pinfunction "VCCO_34_N5") (pintype "power_in"))
      (node (ref "FPGA1") (pin "P2") (pinfunction "VCCO_34_P2") (pintype "power_in"))
      (node (ref "FPGA1") (pin "T6") (pinfunction "VCCO_34_T6") (pintype "power_in"))
      (node (ref "L17") (pin "1") (pinfunction "1_1") (pintype "passive"))
    )
    (net (code "9") (name "2V5") (class "Default")
      (node (ref "C150") (pin "1") (pinfunction "1_1") (pintype "passive"))
      (node (ref "C156") (pin "1") (pinfunction "1_1") (pintype "passive"))
      (node (ref "L15") (pin "2") (pinfunction "2_2") (pintype "passive"))
    )
    (net (code "10") (name "2V5_FPGA") (class "Default")
      (node (ref "C118") (pin "2") (pinfunction "2_2") (pintype "passive"))
      (node (ref "C119") (pin "2") (pinfunction "2_2") (pintype "passive"))
      (node (ref "C134") (pin "2") (pinfunction "2_2") (pintype "passive"))
      (node (ref "C135") (pin "2") (pinfunction "2_2") (pintype "passive"))
      (node (ref "C136") (pin "1") (pinfunction "1_1") (pintype "passive"))
      (node (ref "C137") (pin "2") (pinfunction "2_2") (pintype "passive"))
      (node (ref "C161") (pin "1") (pinfunction "1_1") (pintype "passive"))
      (node (ref "C167") (pin "1") (pinfunction "1_1") (pintype "passive"))
      (node (ref "C172") (pin "2") (pinfunction "2_2") (pintype "passive"))
      (node (ref "FPGA1") (pin "AA1") (pinfunction "VCCO_33_AA1") (pintype "power_in"))
      (node (ref "FPGA1") (pin "AC5") (pinfunction "VCCO_33_AC5") (pintype "power_in"))
      (node (ref "FPGA1") (pin "AD2") (pinfunction "VCCO_33_AD2") (pintype "power_in"))
      (node (ref "FPGA1") (pin "U3") (pinfunction "VCCO_33_U3") (pintype "power_in"))
      (node (ref "FPGA1") (pin "W7") (pinfunction "VCCO_33_W7") (pintype "power_in"))
      (node (ref "FPGA1") (pin "Y4") (pinfunction "VCCO_33_Y4") (pintype "power_in"))
      (node (ref "L15") (pin "1") (pinfunction "1_1") (pintype "passive"))
    )
    (net (code "11") (name "3V3") (class "Default")
      (node (ref "C149") (pin "1") (pinfunction "1_1") (pintype "passive"))
      (node (ref "C155") (pin "1") (pinfunction "1_1") (pintype "passive"))
      (node (ref "L14") (pin "1") (pinfunction "1_1") (pintype "passive"))
    )
    (net (code "12") (name "DVDD_FPGA") (class "Default")
      (node (ref "C100") (pin "1") (pinfunction "1_1") (pintype "passive"))
      (node (ref "C101") (pin "1") (pinfunction "1_1") (pintype "passive"))
      (node (ref "C102") (pin "1") (pinfunction "1_1") (pintype "passive"))
      (node (ref "C103") (pin "1") (pinfunction "1_1") (pintype "passive"))
      (node (ref "C104") (pin "1") (pinfunction "1_1") (pintype "passive"))
      (node (ref "C115") (pin "2") (pinfunction "2_2") (pintype "passive"))
      (node (ref "C116") (pin "2") (pinfunction "2_2") (pintype "passive"))
      (node (ref "C117") (pin "2") (pinfunction "2_2") (pintype "passive"))
      (node (ref "C131") (pin "2") (pinfunction "2_2") (pintype "passive"))
      (node (ref "C132") (pin "2") (pinfunction "2_2") (pintype "passive"))
      (node (ref "C133") (pin "2") (pinfunction "2_2") (pintype "passive"))
      (node (ref "C160") (pin "1") (pinfunction "1_1") (pintype "passive"))
      (node (ref "C166") (pin "1") (pinfunction "1_1") (pintype "passive"))
      (node (ref "C171") (pin "1") (pinfunction "1_1") (pintype "passive"))
      (node (ref "C76") (pin "2") (pinfunction "2_2") (pintype "passive"))
      (node (ref "C80") (pin "1") (pinfunction "1_1") (pintype "passive"))
      (node (ref "C81") (pin "1") (pinfunction "1_1") (pintype "passive"))
      (node (ref "C82") (pin "1") (pinfunction "1_1") (pintype "passive"))
      (node (ref "C83") (pin "1") (pinfunction "1_1") (pintype "passive"))
      (node (ref "C84") (pin "1") (pinfunction "1_1") (pintype "passive"))
      (node (ref "C94") (pin "2") (pinfunction "2_2") (pintype "passive"))
      (node (ref "C98") (pin "1") (pinfunction "1_1") (pintype "passive"))
      (node (ref "C99") (pin "2") (pinfunction "2_2") (pintype "passive"))
      (node (ref "FPGA1") (pin "A21") (pinfunction "VCCO_16_A21") (pintype "power_in"))
      (node (ref "FPGA1") (pin "AC25") (pinfunction "VCCO_13_AC25") (pintype "power_in"))
      (node (ref "FPGA1") (pin "B18") (pinfunction "VCCO_16_B18") (pintype "power_in"))
      (node (ref "FPGA1") (pin "C25") (pinfunction "VCCO_16_C25") (pintype "power_in"))
      (node (ref "FPGA1") (pin "D22") (pinfunction "VCCO_16_D22") (pintype "power_in"))
      (node (ref "FPGA1") (pin "E19") (pinfunction "VCCO_16_E19") (pintype "power_in"))
      (node (ref "FPGA1") (pin "F16") (pinfunction "VCCO_16_F16") (pintype "power_in"))
      (node (ref "FPGA1") (pin "K24") (pinfunction "VCCO_14_K24") (pintype "power_in"))
      (node (ref "FPGA1") (pin "L21") (pinfunction "VCCO_14_L21") (pintype "power_in"))
      (node (ref "FPGA1") (pin "N15") (pinfunction "VCCO_14_N15") (pintype "power_in"))
      (node (ref "FPGA1") (pin "N25") (pinfunction "VCCO_14_N25") (pintype "power_in"))
      (node (ref "FPGA1") (pin "P22") (pinfunction "VCCO_14_P22") (pintype "power_in"))
      (node (ref "FPGA1") (pin "R19") (pinfunction "VCCO_14_R19") (pintype "power_in"))
      (node (ref "FPGA1") (pin "T16") (pinfunction "VCCO_13_T16") (pintype "power_in"))
      (node (ref "FPGA1") (pin "T26") (pinfunction "VCCO_13_T26") (pintype "power_in"))
      (node (ref "FPGA1") (pin "U23") (pinfunction "VCCO_13_U23") (pintype "power_in"))
      (node (ref "FPGA1") (pin "V20") (pinfunction "VCCO_13_V20") (pintype "power_in"))
      (node (ref "FPGA1") (pin "W11") (pinfunction "VCCO_0_W11") (pintype "power_in"))
      (node (ref "FPGA1") (pin "Y14") (pinfunction "VCCO_0_Y14") (pintype "power_in"))
      (node (ref "FPGA1") (pin "Y24") (pinfunction "VCCO_13_Y24") (pintype "power_in"))
      (node (ref "L14") (pin "2") (pinfunction "2_2") (pintype "passive"))
    )
    (net (code "13") (name "GND") (class "Default")
      (node (ref "C100") (pin "2") (pinfunction "2_2") (pintype "passive"))
      (node (ref "C101") (pin "2") (pinfunction "2_2") (pintype "passive"))
      (node (ref "C102") (pin "2") (pinfunction "2_2") (pintype "passive"))
      (node (ref "C103") (pin "2") (pinfunction "2_2") (pintype "passive"))
      (node (ref "C104") (pin "2") (pinfunction "2_2") (pintype "passive"))
      (node (ref "C105") (pin "1") (pinfunction "1_1") (pintype "passive"))
      (node (ref "C106") (pin "1") (pinfunction "1_1") (pintype "passive"))
      (node (ref "C107") (pin "1") (pinfunction "1_1") (pintype "passive"))
      (node (ref "C108") (pin "1") (pinfunction "1_1") (pintype "passive"))
      (node (ref "C109") (pin "1") (pinfunction "1_1") (pintype "passive"))
      (node (ref "C110") (pin "2") (pinfunction "2_2") (pintype "passive"))
      (node (ref "C111") (pin "1") (pinfunction "1_1") (pintype "passive"))
      (node (ref "C112") (pin "1") (pinfunction "1_1") (pintype "passive"))
      (node (ref "C113") (pin "2") (pinfunction "2_2") (pintype "passive"))
      (node (ref "C114") (pin "2") (pinfunction "2_2") (pintype "passive"))
      (node (ref "C115") (pin "1") (pinfunction "1_1") (pintype "passive"))
      (node (ref "C116") (pin "1") (pinfunction "1_1") (pintype "passive"))
      (node (ref "C117") (pin "1") (pinfunction "1_1") (pintype "passive"))
      (node (ref "C118") (pin "1") (pinfunction "1_1") (pintype "passive"))
      (node (ref "C119") (pin "1") (pinfunction "1_1") (pintype "passive"))
      (node (ref "C120") (pin "1") (pinfunction "1_1") (pintype "passive"))
      (node (ref "C121") (pin "1") (pinfunction "1_1") (pintype "passive"))
      (node (ref "C122") (pin "1") (pinfunction "1_1") (pintype "passive"))
      (node (ref "C123") (pin "1") (pinfunction "1_1") (pintype "passive"))
      (node (ref "C124") (pin "1") (pinfunction "1_1") (pintype "passive"))
      (node (ref "C125") (pin "1") (pinfunction "1_1") (pintype "passive"))
      (node (ref "C126") (pin "2") (pinfunction "2_2") (pintype "passive"))
      (node (ref "C127") (pin "2") (pinfunction "2_2") (pintype "passive"))
      (node (ref "C128") (pin "1") (pinfunction "1_1") (pintype "passive"))
      (node (ref "C129") (pin "2") (pinfunction "2_2") (pintype "passive"))
      (node (ref "C130") (pin "1") (pinfunction "1_1") (pintype "passive"))
      (node (ref "C131") (pin "1") (pinfunction "1_1") (pintype "passive"))
      (node (ref "C132") (pin "1") (pinfunction "1_1") (pintype "passive"))
      (node (ref "C133") (pin "1") (pinfunction "1_1") (pintype "passive"))
      (node (ref "C134") (pin "1") (pinfunction "1_1") (pintype "passive"))
      (node (ref "C135") (pin "1") (pinfunction "1_1") (pintype "passive"))
      (node (ref "C136") (pin "2") (pinfunction "2_2") (pintype "passive"))
      (node (ref "C137") (pin "1") (pinfunction "1_1") (pintype "passive"))
      (node (ref "C138") (pin "1") (pinfunction "1_1") (pintype "passive"))
      (node (ref "C139") (pin "1") (pinfunction "1_1") (pintype "passive"))
      (node (ref "C140") (pin "1") (pinfunction "1_1") (pintype "passive"))
      (node (ref "C141") (pin "1") (pinfunction "1_1") (pintype "passive"))
      (node (ref "C142") (pin "1") (pinfunction "1_1") (pintype "passive"))
      (node (ref "C143") (pin "1") (pinfunction "1_1") (pintype "passive"))
      (node (ref "C144") (pin "2") (pinfunction "2_2") (pintype "passive"))
      (node (ref "C145") (pin "1") (pinfunction "1_1") (pintype "passive"))
      (node (ref "C146") (pin "1") (pinfunction "1_1") (pintype "passive"))
      (node (ref "C147") (pin "1") (pinfunction "1_1") (pintype "passive"))
      (node (ref "C148") (pin "2") (pinfunction "2_2") (pintype "passive"))
      (node (ref "C149") (pin "2") (pinfunction "2_2") (pintype "passive"))
      (node (ref "C150") (pin "2") (pinfunction "2_2") (pintype "passive"))
      (node (ref "C151") (pin "2") (pinfunction "2_2") (pintype "passive"))
      (node (ref "C152") (pin "1") (pinfunction "1_1") (pintype "passive"))
      (node (ref "C153") (pin "1") (pinfunction "1_1") (pintype "passive"))
      (node (ref "C154") (pin "2") (pinfunction "2_2") (pintype "passive"))
      (node (ref "C155") (pin "2") (pinfunction "2_2") (pintype "passive"))
      (node (ref "C156") (pin "2") (pinfunction "2_2") (pintype "passive"))
      (node (ref "C157") (pin "2") (pinfunction "2_2") (pintype "passive"))
      (node (ref "C158") (pin "2") (pinfunction "2_2") (pintype "passive"))
      (node (ref "C159") (pin "2") (pinfunction "2_2") (pintype "passive"))
      (node (ref "C160") (pin "2") (pinfunction "2_2") (pintype "passive"))
      (node (ref "C161") (pin "2") (pinfunction "2_2") (pintype "passive"))
      (node (ref "C162") (pin "2") (pinfunction "2_2") (pintype "passive"))
      (node (ref "C163") (pin "2") (pinfunction "2_2") (pintype "passive"))
      (node (ref "C165") (pin "2") (pinfunction "2_2") (pintype "passive"))
      (node (ref "C166") (pin "2") (pinfunction "2_2") (pintype "passive"))
      (node (ref "C167") (pin "2") (pinfunction "2_2") (pintype "passive"))
      (node (ref "C168") (pin "2") (pinfunction "2_2") (pintype "passive"))
      (node (ref "C169") (pin "2") (pinfunction "2_2") (pintype "passive"))
      (node (ref "C170") (pin "1") (pinfunction "1_1") (pintype "passive"))
      (node (ref "C171") (pin "2") (pinfunction "2_2") (pintype "passive"))
      (node (ref "C172") (pin "1") (pinfunction "1_1") (pintype "passive"))
      (node (ref "C173") (pin "1") (pinfunction "1_1") (pintype "passive"))
      (node (ref "C174") (pin "2") (pinfunction "2_2") (pintype "passive"))
      (node (ref "C76") (pin "1") (pinfunction "1_1") (pintype "passive"))
      (node (ref "C77") (pin "2") (pinfunction "2_2") (pintype "passive"))
      (node (ref "C78") (pin "2") (pinfunction "2_2") (pintype "passive"))
      (node (ref "C79") (pin "2") (pinfunction "2_2") (pintype "passive"))
      (node (ref "C80") (pin "2") (pinfunction "2_2") (pintype "passive"))
      (node (ref "C81") (pin "2") (pinfunction "2_2") (pintype "passive"))
      (node (ref "C82") (pin "2") (pinfunction "2_2") (pintype "passive"))
      (node (ref "C83") (pin "2") (pinfunction "2_2") (pintype "passive"))
      (node (ref "C84") (pin "2") (pinfunction "2_2") (pintype "passive"))
      (node (ref "C85") (pin "1") (pinfunction "1_1") (pintype "passive"))
      (node (ref "C86") (pin "1") (pinfunction "1_1") (pintype "passive"))
      (node (ref "C87") (pin "1") (pinfunction "1_1") (pintype "passive"))
      (node (ref "C88") (pin "2") (pinfunction "2_2") (pintype "passive"))
      (node (ref "C89") (pin "2") (pinfunction "2_2") (pintype "passive"))
      (node (ref "C90") (pin "2") (pinfunction "2_2") (pintype "passive"))
      (node (ref "C91") (pin "2") (pinfunction "2_2") (pintype "passive"))
      (node (ref "C92") (pin "1") (pinfunction "1_1") (pintype "passive"))
      (node (ref "C93") (pin "2") (pinfunction "2_2") (pintype "passive"))
      (node (ref "C94") (pin "1") (pinfunction "1_1") (pintype "passive"))
      (node (ref "C95") (pin "2") (pinfunction "2_2") (pintype "passive"))
      (node (ref "C96") (pin "2") (pinfunction "2_2") (pintype "passive"))
      (node (ref "C97") (pin "2") (pinfunction "2_2") (pintype "passive"))
      (node (ref "C98") (pin "2") (pinfunction "2_2") (pintype "passive"))
      (node (ref "C99") (pin "1") (pinfunction "1_1") (pintype "passive"))
      (node (ref "FPGA1") (pin "A10") (pinfunction "GND_A10") (pintype "power_in"))
      (node (ref "FPGA1") (pin "A12") (pinfunction "GND_A12") (pintype "power_in"))
      (node (ref "FPGA1") (pin "A14") (pinfunction "GND_A14") (pintype "power_in"))
      (node (ref "FPGA1") (pin "A16") (pinfunction "GND_A16") (pintype "power_in"))
      (node (ref "FPGA1") (pin "A26") (pinfunction "GND_A26") (pintype "power_in"))
      (node (ref "FPGA1") (pin "A6") (pinfunction "GND_A6") (pintype "power_in"))
      (node (ref "FPGA1") (pin "A8") (pinfunction "GND_A8") (pintype "power_in"))
      (node (ref "FPGA1") (pin "AA14") (pinfunction "GND_AA14") (pintype "power_in"))
      (node (ref "FPGA1") (pin "AA16") (pinfunction "GND_AA16") (pintype "power_in"))
      (node (ref "FPGA1") (pin "AA26") (pinfunction "GND_AA26") (pintype "power_in"))
      (node (ref "FPGA1") (pin "AA6") (pinfunction "GND_AA6") (pintype "power_in"))
      (node (ref "FPGA1") (pin "AA9") (pinfunction "GND_AA9") (pintype "power_in"))
      (node (ref "FPGA1") (pin "AB10") (pinfunction "GND_AB10") (pintype "power_in"))
      (node (ref "FPGA1") (pin "AB12") (pinfunction "GND_AB12") (pintype "power_in"))
      (node (ref "FPGA1") (pin "AB14") (pinfunction "GND_AB14") (pintype "power_in"))
      (node (ref "FPGA1") (pin "AB23") (pinfunction "GND_AB23") (pintype "power_in"))
      (node (ref "FPGA1") (pin "AB3") (pinfunction "GND_AB3") (pintype "power_in"))
      (node (ref "FPGA1") (pin "AB8") (pinfunction "GND_AB8") (pintype "power_in"))
      (node (ref "FPGA1") (pin "AB9") (pinfunction "GND_AB9") (pintype "power_in"))
      (node (ref "FPGA1") (pin "AC15") (pinfunction "GND_AC15") (pintype "power_in"))
      (node (ref "FPGA1") (pin "AC20") (pinfunction "GND_AC20") (pintype "power_in"))
      (node (ref "FPGA1") (pin "AC7") (pinfunction "GND_AC7") (pintype "power_in"))
      (node (ref "FPGA1") (pin "AD11") (pinfunction "GND_AD11") (pintype "power_in"))
      (node (ref "FPGA1") (pin "AD13") (pinfunction "GND_AD13") (pintype "power_in"))
      (node (ref "FPGA1") (pin "AD16") (pinfunction "GND_AD16") (pintype "power_in"))
      (node (ref "FPGA1") (pin "AD6") (pinfunction "GND_AD6") (pintype "power_in"))
      (node (ref "FPGA1") (pin "AD9") (pinfunction "GND_AD9") (pintype "power_in"))
      (node (ref "FPGA1") (pin "AE15") (pinfunction "GND_AE15") (pintype "power_in"))
      (node (ref "FPGA1") (pin "AE24") (pinfunction "GND_AE24") (pintype "power_in"))
      (node (ref "FPGA1") (pin "AE4") (pinfunction "GND_AE4") (pintype "power_in"))
      (node (ref "FPGA1") (pin "AE6") (pinfunction "GND_AE6") (pintype "power_in"))
      (node (ref "FPGA1") (pin "AF1") (pinfunction "GND_AF1") (pintype "power_in"))
      (node (ref "FPGA1") (pin "AF10") (pinfunction "GND_AF10") (pintype "power_in"))
      (node (ref "FPGA1") (pin "AF12") (pinfunction "GND_AF12") (pintype "power_in"))
      (node (ref "FPGA1") (pin "AF14") (pinfunction "GND_AF14") (pintype "power_in"))
      (node (ref "FPGA1") (pin "AF16") (pinfunction "GND_AF16") (pintype "power_in"))
      (node (ref "FPGA1") (pin "AF21") (pinfunction "GND_AF21") (pintype "power_in"))
      (node (ref "FPGA1") (pin "AF6") (pinfunction "GND_AF6") (pintype "power_in"))
      (node (ref "FPGA1") (pin "AF8") (pinfunction "GND_AF8") (pintype "power_in"))
      (node (ref "FPGA1") (pin "B15") (pinfunction "GND_B15") (pintype "power_in"))
      (node (ref "FPGA1") (pin "B16") (pinfunction "GND_B16") (pintype "power_in"))
      (node (ref "FPGA1") (pin "B23") (pinfunction "GND_B23") (pintype "power_in"))
      (node (ref "FPGA1") (pin "B3") (pinfunction "GND_B3") (pintype "power_in"))
      (node (ref "FPGA1") (pin "B6") (pinfunction "GND_B6") (pintype "power_in"))
      (node (ref "FPGA1") (pin "C11") (pinfunction "GND_C11") (pintype "power_in"))
      (node (ref "FPGA1") (pin "C13") (pinfunction "GND_C13") (pintype "power_in"))
      (node (ref "FPGA1") (pin "C16") (pinfunction "GND_C16") (pintype "power_in"))
      (node (ref "FPGA1") (pin "C20") (pinfunction "GND_C20") (pintype "power_in"))
      (node (ref "FPGA1") (pin "C6") (pinfunction "GND_C6") (pintype "power_in"))
      (node (ref "FPGA1") (pin "C9") (pinfunction "GND_C9") (pintype "power_in"))
      (node (ref "FPGA1") (pin "D15") (pinfunction "GND_D15") (pintype "power_in"))
      (node (ref "FPGA1") (pin "D17") (pinfunction "GND_D17") (pintype "power_in"))
      (node (ref "FPGA1") (pin "D7") (pinfunction "GND_D7") (pintype "power_in"))
      (node (ref "FPGA1") (pin "E10") (pinfunction "GND_E10") (pintype "power_in"))
      (node (ref "FPGA1") (pin "E12") (pinfunction "GND_E12") (pintype "power_in"))
      (node (ref "FPGA1") (pin "E14") (pinfunction "GND_E14") (pintype "power_in"))
      (node (ref "FPGA1") (pin "E15") (pinfunction "GND_E15") (pintype "power_in"))
      (node (ref "FPGA1") (pin "E24") (pinfunction "GND_E24") (pintype "power_in"))
      (node (ref "FPGA1") (pin "E4") (pinfunction "GND_E4") (pintype "power_in"))
      (node (ref "FPGA1") (pin "E7") (pinfunction "GND_E7") (pintype "power_in"))
      (node (ref "FPGA1") (pin "E8") (pinfunction "GND_E8") (pintype "power_in"))
      (node (ref "FPGA1") (pin "E9") (pinfunction "GND_E9") (pintype "power_in"))
      (node (ref "FPGA1") (pin "F1") (pinfunction "GND_F1") (pintype "power_in"))
      (node (ref "FPGA1") (pin "F14") (pinfunction "GND_F14") (pintype "power_in"))
      (node (ref "FPGA1") (pin "F21") (pinfunction "GND_F21") (pintype "power_in"))
      (node (ref "FPGA1") (pin "F9") (pinfunction "GND_F9") (pintype "power_in"))
      (node (ref "FPGA1") (pin "G10") (pinfunction "GND_G10") (pintype "power_in"))
      (node (ref "FPGA1") (pin "G11") (pinfunction "GND_G11") (pintype "power_in"))
      (node (ref "FPGA1") (pin "G12") (pinfunction "GND_G12") (pintype "power_in"))
      (node (ref "FPGA1") (pin "G13") (pinfunction "GND_G13") (pintype "power_in"))
      (node (ref "FPGA1") (pin "G14") (pinfunction "VCCBATT_0_G14") (pintype "power_in"))
      (node (ref "FPGA1") (pin "G18") (pinfunction "GND_G18") (pintype "power_in"))
      (node (ref "FPGA1") (pin "H25") (pinfunction "GND_H25") (pintype "power_in"))
      (node (ref "FPGA1") (pin "H5") (pinfunction "GND_H5") (pintype "power_in"))
      (node (ref "FPGA1") (pin "J12") (pinfunction "GND_J12") (pintype "power_in"))
      (node (ref "FPGA1") (pin "J2") (pinfunction "GND_J2") (pintype "power_in"))
      (node (ref "FPGA1") (pin "J22") (pinfunction "GND_J22") (pintype "power_in"))
      (node (ref "FPGA1") (pin "K11") (pinfunction "GND_K11") (pintype "power_in"))
      (node (ref "FPGA1") (pin "K13") (pinfunction "GND_K13") (pintype "power_in"))
      (node (ref "FPGA1") (pin "K19") (pinfunction "GND_K19") (pintype "power_in"))
      (node (ref "FPGA1") (pin "K9") (pinfunction "GND_K9") (pintype "power_in"))
      (node (ref "FPGA1") (pin "L10") (pinfunction "GND_L10") (pintype "power_in"))
      (node (ref "FPGA1") (pin "L12") (pinfunction "GND_L12") (pintype "power_in"))
      (node (ref "FPGA1") (pin "L16") (pinfunction "GND_L16") (pintype "power_in"))
      (node (ref "FPGA1") (pin "L26") (pinfunction "GND_L26") (pintype "power_in"))
      (node (ref "FPGA1") (pin "L6") (pinfunction "GND_L6") (pintype "power_in"))
      (node (ref "FPGA1") (pin "M13") (pinfunction "GND_M13") (pintype "power_in"))
      (node (ref "FPGA1") (pin "M23") (pinfunction "GND_M23") (pintype "power_in"))
      (node (ref "FPGA1") (pin "M3") (pinfunction "GND_M3") (pintype "power_in"))
      (node (ref "FPGA1") (pin "M9") (pinfunction "GND_M9") (pintype "power_in"))
      (node (ref "FPGA1") (pin "N10") (pinfunction "GND_N10") (pintype "power_in"))
      (node (ref "FPGA1") (pin "N20") (pinfunction "GND_N20") (pintype "power_in"))
      (node (ref "FPGA1") (pin "P13") (pinfunction "GND_P13") (pintype "power_in"))
      (node (ref "FPGA1") (pin "P17") (pinfunction "GND_P17") (pintype "power_in"))
      (node (ref "FPGA1") (pin "P7") (pinfunction "GND_P7") (pintype "power_in"))
      (node (ref "FPGA1") (pin "P9") (pinfunction "GND_P9") (pintype "power_in"))
      (node (ref "FPGA1") (pin "R10") (pinfunction "GND_R10") (pintype "power_in"))
      (node (ref "FPGA1") (pin "R24") (pinfunction "GND_R24") (pintype "power_in"))
      (node (ref "FPGA1") (pin "R4") (pinfunction "GND_R4") (pintype "power_in"))
      (node (ref "FPGA1") (pin "T1") (pinfunction "GND_T1") (pintype "power_in"))
      (node (ref "FPGA1") (pin "T11") (pinfunction "GND_T11") (pintype "power_in"))
      (node (ref "FPGA1") (pin "T13") (pinfunction "GND_T13") (pintype "power_in"))
      (node (ref "FPGA1") (pin "T21") (pinfunction "GND_T21") (pintype "power_in"))
      (node (ref "FPGA1") (pin "T9") (pinfunction "GND_T9") (pintype "power_in"))
      (node (ref "FPGA1") (pin "U10") (pinfunction "GND_U10") (pintype "power_in"))
      (node (ref "FPGA1") (pin "U12") (pinfunction "GND_U12") (pintype "power_in"))
      (node (ref "FPGA1") (pin "U18") (pinfunction "GND_U18") (pintype "power_in"))
      (node (ref "FPGA1") (pin "U8") (pinfunction "GND_U8") (pintype "power_in"))
      (node (ref "FPGA1") (pin "V13") (pinfunction "GND_V13") (pintype "power_in"))
      (node (ref "FPGA1") (pin "V15") (pinfunction "GND_V15") (pintype "power_in"))
      (node (ref "FPGA1") (pin "V25") (pinfunction "GND_V25") (pintype "power_in"))
      (node (ref "FPGA1") (pin "V5") (pinfunction "GND_V5") (pintype "power_in"))
      (node (ref "FPGA1") (pin "W12") (pinfunction "GND_W12") (pintype "power_in"))
      (node (ref "FPGA1") (pin "W2") (pinfunction "GND_W2") (pintype "power_in"))
      (node (ref "FPGA1") (pin "W22") (pinfunction "GND_W22") (pintype "power_in"))
      (node (ref "FPGA1") (pin "Y10") (pinfunction "GND_Y10") (pintype "power_in"))
      (node (ref "FPGA1") (pin "Y11") (pinfunction "GND_Y11") (pintype "power_in"))
      (node (ref "FPGA1") (pin "Y12") (pinfunction "GND_Y12") (pintype "power_in"))
      (node (ref "FPGA1") (pin "Y13") (pinfunction "GND_Y13") (pintype "power_in"))
      (node (ref "FPGA1") (pin "Y19") (pinfunction "GND_Y19") (pintype "power_in"))
      (node (ref "L19") (pin "1") (pinfunction "1_1") (pintype "passive"))
    )
    (net (code "14") (name "GND_XADC") (class "Default")
      (node (ref "C164") (pin "2") (pinfunction "2_2") (pintype "passive"))
      (node (ref "FPGA1") (pin "M11") (pinfunction "GNDADC_0_M11") (pintype "power_in"))
      (node (ref "L19") (pin "2") (pinfunction "2_2") (pintype "passive"))
    )
    (net (code "15") (name "VCC_XADC") (class "Default")
      (node (ref "C164") (pin "1") (pinfunction "1_1") (pintype "passive"))
      (node (ref "FPGA1") (pin "M12") (pinfunction "VCCADC_0_M12") (pintype "power_in"))
      (node (ref "L18") (pin "1") (pinfunction "1_1") (pintype "passive"))
    )
  )
)
